# MIDI_Signal_Contidioner.net
KiCad netlist of a schematic drawn in EAGLE
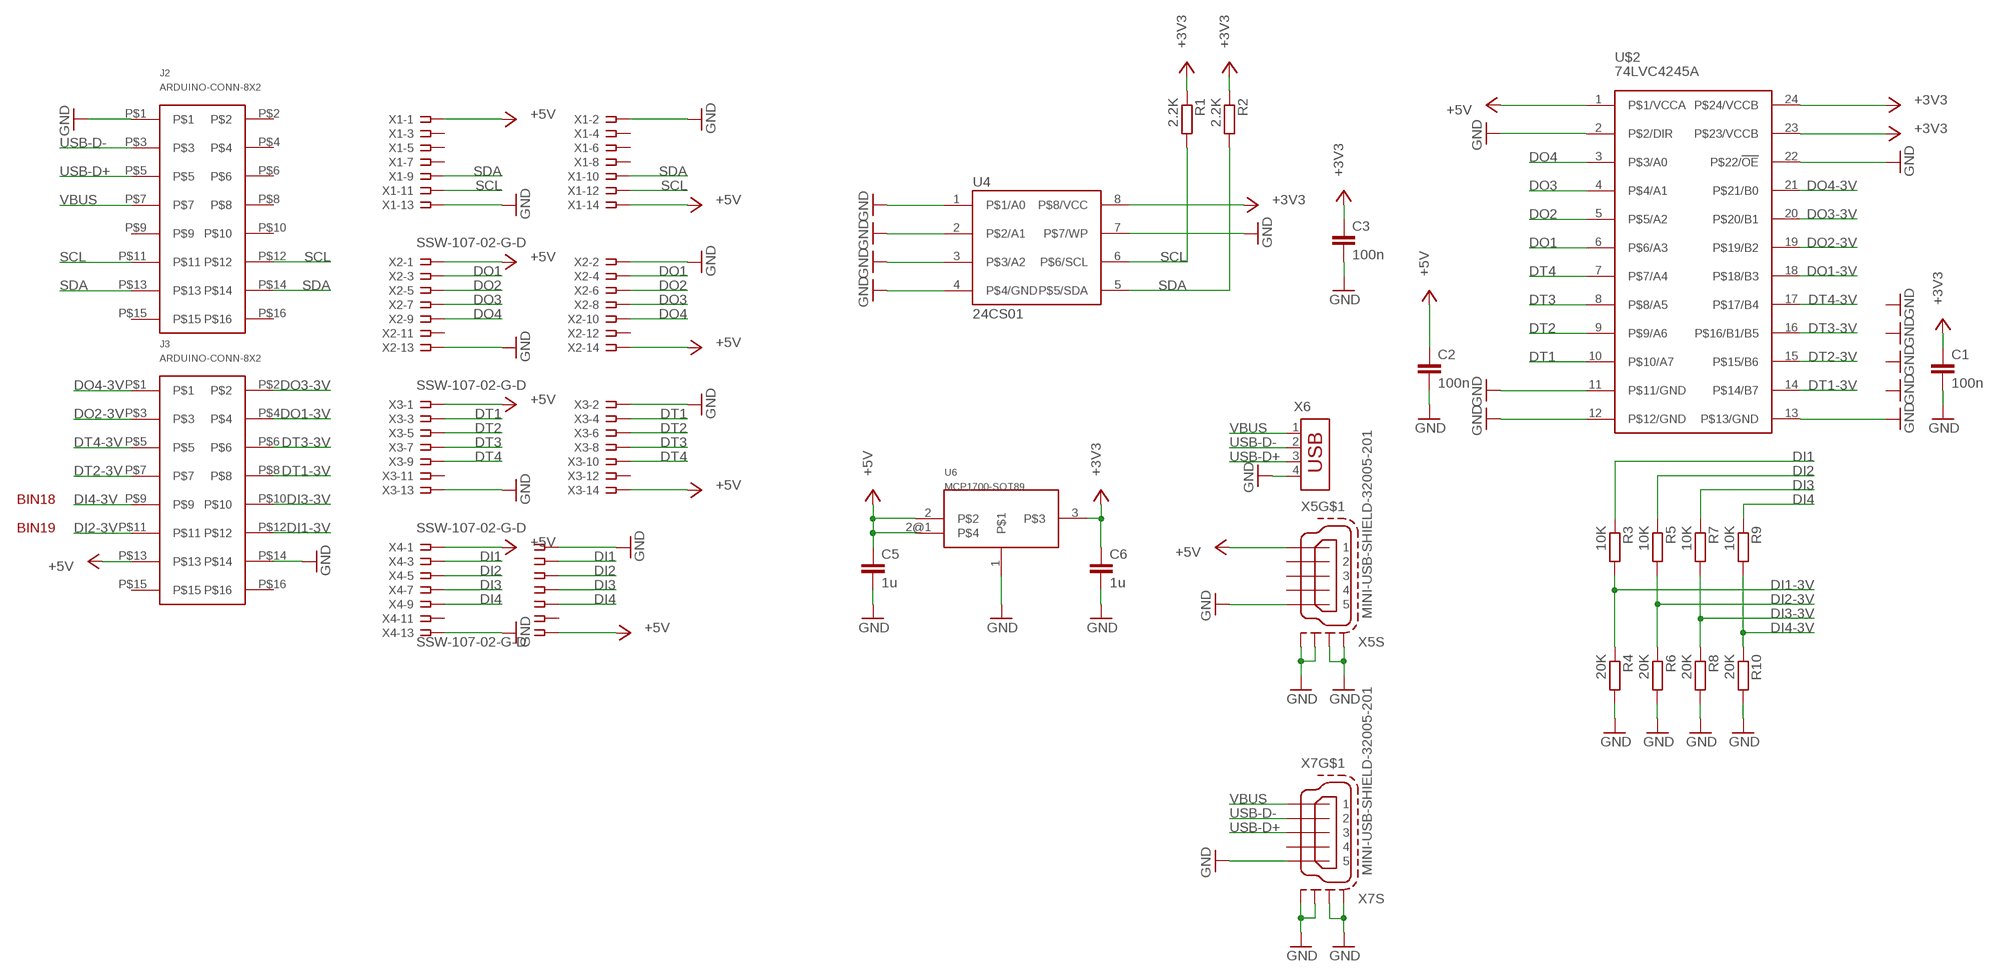
[diagram p0: schematic, sheet 1]

(export (version "E")
  (design (tool "Eeschema 10.0.6"))
  (components
    (comp (ref "C1")
      (value "100n")
      (footprint "eagle-import:C0805")
      (libsource (lib "eagle-import") (part "C-EUC0805"))
    )
    (comp (ref "C2")
      (value "100n")
      (footprint "eagle-import:C0805")
      (libsource (lib "eagle-import") (part "C-EUC0805"))
    )
    (comp (ref "C3")
      (value "100n")
      (footprint "eagle-import:C0805")
      (libsource (lib "eagle-import") (part "C-EUC0805"))
    )
    (comp (ref "C5")
      (value "1u")
      (footprint "eagle-import:C0805")
      (libsource (lib "eagle-import") (part "C-EUC0805"))
    )
    (comp (ref "C6")
      (value "1u")
      (footprint "eagle-import:C0805")
      (libsource (lib "eagle-import") (part "C-EUC0805"))
    )
    (comp (ref "J2")
      (value "ARDUINO-CONN-8X2")
      (footprint "eagle-import:ARDUINO-CONN-8X2")
      (libsource (lib "eagle-import") (part "ARDUINO-CONN-8X2"))
    )
    (comp (ref "J3")
      (value "ARDUINO-CONN-8X2")
      (footprint "eagle-import:ARDUINO-CONN-8X2")
      (libsource (lib "eagle-import") (part "ARDUINO-CONN-8X2"))
    )
    (comp (ref "R1")
      (value "2.2K")
      (footprint "eagle-import:R0805W")
      (libsource (lib "eagle-import") (part "R-EU_R0805W"))
    )
    (comp (ref "R2")
      (value "2.2K")
      (footprint "eagle-import:R0805W")
      (libsource (lib "eagle-import") (part "R-EU_R0805W"))
    )
    (comp (ref "R3")
      (value "10K")
      (footprint "eagle-import:R0805W")
      (libsource (lib "eagle-import") (part "R-EU_R0805W"))
    )
    (comp (ref "R4")
      (value "20K")
      (footprint "eagle-import:R0805W")
      (libsource (lib "eagle-import") (part "R-EU_R0805W"))
    )
    (comp (ref "R5")
      (value "10K")
      (footprint "eagle-import:R0805W")
      (libsource (lib "eagle-import") (part "R-EU_R0805W"))
    )
    (comp (ref "R6")
      (value "20K")
      (footprint "eagle-import:R0805W")
      (libsource (lib "eagle-import") (part "R-EU_R0805W"))
    )
    (comp (ref "R7")
      (value "10K")
      (footprint "eagle-import:R0805W")
      (libsource (lib "eagle-import") (part "R-EU_R0805W"))
    )
    (comp (ref "R8")
      (value "20K")
      (footprint "eagle-import:R0805W")
      (libsource (lib "eagle-import") (part "R-EU_R0805W"))
    )
    (comp (ref "R9")
      (value "10K")
      (footprint "eagle-import:R0805W")
      (libsource (lib "eagle-import") (part "R-EU_R0805W"))
    )
    (comp (ref "R10")
      (value "20K")
      (footprint "eagle-import:R0805W")
      (libsource (lib "eagle-import") (part "R-EU_R0805W"))
    )
    (comp (ref "U$2")
      (value "74LVC4245A")
      (footprint "eagle-import:74LVC4245A-SO24")
      (libsource (lib "eagle-import") (part "74LVC4245A"))
    )
    (comp (ref "U4")
      (value "24CS01")
      (footprint "eagle-import:24CS01-SO8")
      (libsource (lib "eagle-import") (part "24CS01"))
    )
    (comp (ref "U6")
      (value "MCP1700-SOT89")
      (footprint "eagle-import:MCP1700-SOT89")
      (libsource (lib "eagle-import") (part "MCP1700-SOT89"))
    )
    (comp (ref "X1")
      (value "SSW-107-02-G-D")
      (footprint "eagle-import:SSW-107-02-G-D")
      (fields (field (name "MF") "Samtec Inc."))
      (libsource (lib "eagle-import") (part "SSW-107-02-G-D"))
    )
    (comp (ref "X2")
      (value "SSW-107-02-G-D")
      (footprint "eagle-import:SSW-107-02-G-D")
      (fields (field (name "MF") "Samtec Inc."))
      (libsource (lib "eagle-import") (part "SSW-107-02-G-D"))
    )
    (comp (ref "X3")
      (value "SSW-107-02-G-D")
      (footprint "eagle-import:SSW-107-02-G-D")
      (fields (field (name "MF") "Samtec Inc."))
      (libsource (lib "eagle-import") (part "SSW-107-02-G-D"))
    )
    (comp (ref "X4")
      (value "SSW-107-02-G-D")
      (footprint "eagle-import:SSW-107-02-G-D")
      (fields (field (name "MF") "Samtec Inc."))
      (libsource (lib "eagle-import") (part "SSW-107-02-G-D"))
    )
    (comp (ref "X5")
      (value "MINI-USB-SHIELD-32005-201")
      (footprint "eagle-import:MINI-USB-32005-201")
      (libsource (lib "eagle-import") (part "MINI-USB-SHIELD-32005-201"))
    )
    (comp (ref "X6")
      (value "USB-787616")
      (footprint "eagle-import:USB")
      (libsource (lib "eagle-import") (part "USB-787616"))
    )
    (comp (ref "X7")
      (value "MINI-USB-SHIELD-32005-201")
      (footprint "eagle-import:MINI-USB-32005-201")
      (libsource (lib "eagle-import") (part "MINI-USB-SHIELD-32005-201"))
    )
  )
  (nets
    (net (code "1") (name "+3V3") (class "Default")
      (node (ref "C1") (pin "1") (pinfunction "1_1") (pintype "passive"))
      (node (ref "C3") (pin "1") (pinfunction "1_1") (pintype "passive"))
      (node (ref "C6") (pin "1") (pinfunction "1_1") (pintype "passive"))
      (node (ref "R1") (pin "1") (pinfunction "1_1") (pintype "passive"))
      (node (ref "R2") (pin "1") (pinfunction "1_1") (pintype "passive"))
      (node (ref "U$2") (pin "23") (pinfunction "P$23/VCCB_23") (pintype "bidirectional"))
      (node (ref "U$2") (pin "24") (pinfunction "P$24/VCCB_24") (pintype "bidirectional"))
      (node (ref "U4") (pin "8") (pinfunction "P$8/VCC_8") (pintype "bidirectional"))
      (node (ref "U6") (pin "3") (pinfunction "P$3_3") (pintype "bidirectional"))
    )
    (net (code "2") (name "+5V") (class "Default")
      (node (ref "C2") (pin "1") (pinfunction "1_1") (pintype "passive"))
      (node (ref "C5") (pin "1") (pinfunction "1_1") (pintype "passive"))
      (node (ref "J3") (pin "P$13") (pinfunction "P$13_P$13") (pintype "bidirectional"))
      (node (ref "U$2") (pin "1") (pinfunction "P$1/VCCA_1") (pintype "bidirectional"))
      (node (ref "U6") (pin "2") (pinfunction "P$2_2") (pintype "bidirectional"))
      (node (ref "U6") (pin "2@1") (pinfunction "P$4_2@1") (pintype "bidirectional"))
      (node (ref "X1") (pin "1") (pinfunction "1_1") (pintype "passive"))
      (node (ref "X1") (pin "14") (pinfunction "1_14") (pintype "passive"))
      (node (ref "X2") (pin "1") (pinfunction "1_1") (pintype "passive"))
      (node (ref "X2") (pin "14") (pinfunction "1_14") (pintype "passive"))
      (node (ref "X3") (pin "1") (pinfunction "1_1") (pintype "passive"))
      (node (ref "X3") (pin "14") (pinfunction "1_14") (pintype "passive"))
      (node (ref "X4") (pin "1") (pinfunction "1_1") (pintype "passive"))
      (node (ref "X4") (pin "14") (pinfunction "1_14") (pintype "passive"))
      (node (ref "X5") (pin "1") (pinfunction "1_1") (pintype "passive"))
    )
    (net (code "3") (name "/DI1") (class "Default")
      (node (ref "R3") (pin "1") (pinfunction "1_1") (pintype "passive"))
      (node (ref "X4") (pin "3") (pinfunction "1_3") (pintype "passive"))
      (node (ref "X4") (pin "4") (pinfunction "1_4") (pintype "passive"))
    )
    (net (code "4") (name "/DI1-3V") (class "Default")
      (node (ref "J3") (pin "P$12") (pinfunction "P$12_P$12") (pintype "bidirectional"))
      (node (ref "R3") (pin "2") (pinfunction "2_2") (pintype "passive"))
      (node (ref "R4") (pin "1") (pinfunction "1_1") (pintype "passive"))
    )
    (net (code "5") (name "/DI2") (class "Default")
      (node (ref "R5") (pin "1") (pinfunction "1_1") (pintype "passive"))
      (node (ref "X4") (pin "5") (pinfunction "1_5") (pintype "passive"))
      (node (ref "X4") (pin "6") (pinfunction "1_6") (pintype "passive"))
    )
    (net (code "6") (name "/DI2-3V") (class "Default")
      (node (ref "J3") (pin "P$11") (pinfunction "P$11_P$11") (pintype "bidirectional"))
      (node (ref "R5") (pin "2") (pinfunction "2_2") (pintype "passive"))
      (node (ref "R6") (pin "1") (pinfunction "1_1") (pintype "passive"))
    )
    (net (code "7") (name "/DI3") (class "Default")
      (node (ref "R7") (pin "1") (pinfunction "1_1") (pintype "passive"))
      (node (ref "X4") (pin "7") (pinfunction "1_7") (pintype "passive"))
      (node (ref "X4") (pin "8") (pinfunction "1_8") (pintype "passive"))
    )
    (net (code "8") (name "/DI3-3V") (class "Default")
      (node (ref "J3") (pin "P$10") (pinfunction "P$10_P$10") (pintype "bidirectional"))
      (node (ref "R7") (pin "2") (pinfunction "2_2") (pintype "passive"))
      (node (ref "R8") (pin "1") (pinfunction "1_1") (pintype "passive"))
    )
    (net (code "9") (name "/DI4") (class "Default")
      (node (ref "R9") (pin "1") (pinfunction "1_1") (pintype "passive"))
      (node (ref "X4") (pin "10") (pinfunction "1_10") (pintype "passive"))
      (node (ref "X4") (pin "9") (pinfunction "1_9") (pintype "passive"))
    )
    (net (code "10") (name "/DI4-3V") (class "Default")
      (node (ref "J3") (pin "P$9") (pinfunction "P$9_P$9") (pintype "bidirectional"))
      (node (ref "R10") (pin "1") (pinfunction "1_1") (pintype "passive"))
      (node (ref "R9") (pin "2") (pinfunction "2_2") (pintype "passive"))
    )
    (net (code "11") (name "/DO1") (class "Default")
      (node (ref "U$2") (pin "6") (pinfunction "P$6/A3_6") (pintype "bidirectional"))
      (node (ref "X2") (pin "3") (pinfunction "1_3") (pintype "passive"))
      (node (ref "X2") (pin "4") (pinfunction "1_4") (pintype "passive"))
    )
    (net (code "12") (name "/DO1-3V") (class "Default")
      (node (ref "J3") (pin "P$4") (pinfunction "P$4_P$4") (pintype "bidirectional"))
      (node (ref "U$2") (pin "18") (pinfunction "P$18/B3_18") (pintype "bidirectional"))
    )
    (net (code "13") (name "/DO2") (class "Default")
      (node (ref "U$2") (pin "5") (pinfunction "P$5/A2_5") (pintype "bidirectional"))
      (node (ref "X2") (pin "5") (pinfunction "1_5") (pintype "passive"))
      (node (ref "X2") (pin "6") (pinfunction "1_6") (pintype "passive"))
    )
    (net (code "14") (name "/DO2-3V") (class "Default")
      (node (ref "J3") (pin "P$3") (pinfunction "P$3_P$3") (pintype "bidirectional"))
      (node (ref "U$2") (pin "19") (pinfunction "P$19/B2_19") (pintype "bidirectional"))
    )
    (net (code "15") (name "/DO3") (class "Default")
      (node (ref "U$2") (pin "4") (pinfunction "P$4/A1_4") (pintype "bidirectional"))
      (node (ref "X2") (pin "7") (pinfunction "1_7") (pintype "passive"))
      (node (ref "X2") (pin "8") (pinfunction "1_8") (pintype "passive"))
    )
    (net (code "16") (name "/DO3-3V") (class "Default")
      (node (ref "J3") (pin "P$2") (pinfunction "P$2_P$2") (pintype "bidirectional"))
      (node (ref "U$2") (pin "20") (pinfunction "P$20/B1_20") (pintype "bidirectional"))
    )
    (net (code "17") (name "/DO4") (class "Default")
      (node (ref "U$2") (pin "3") (pinfunction "P$3/A0_3") (pintype "bidirectional"))
      (node (ref "X2") (pin "10") (pinfunction "1_10") (pintype "passive"))
      (node (ref "X2") (pin "9") (pinfunction "1_9") (pintype "passive"))
    )
    (net (code "18") (name "/DO4-3V") (class "Default")
      (node (ref "J3") (pin "P$1") (pinfunction "P$1_P$1") (pintype "bidirectional"))
      (node (ref "U$2") (pin "21") (pinfunction "P$21/B0_21") (pintype "bidirectional"))
    )
    (net (code "19") (name "/DT1") (class "Default")
      (node (ref "U$2") (pin "10") (pinfunction "P$10/A7_10") (pintype "bidirectional"))
      (node (ref "X3") (pin "3") (pinfunction "1_3") (pintype "passive"))
      (node (ref "X3") (pin "4") (pinfunction "1_4") (pintype "passive"))
    )
    (net (code "20") (name "/DT1-3V") (class "Default")
      (node (ref "J3") (pin "P$8") (pinfunction "P$8_P$8") (pintype "bidirectional"))
      (node (ref "U$2") (pin "14") (pinfunction "P$14/B7_14") (pintype "bidirectional"))
    )
    (net (code "21") (name "/DT2") (class "Default")
      (node (ref "U$2") (pin "9") (pinfunction "P$9/A6_9") (pintype "bidirectional"))
      (node (ref "X3") (pin "5") (pinfunction "1_5") (pintype "passive"))
      (node (ref "X3") (pin "6") (pinfunction "1_6") (pintype "passive"))
    )
    (net (code "22") (name "/DT2-3V") (class "Default")
      (node (ref "J3") (pin "P$7") (pinfunction "P$7_P$7") (pintype "bidirectional"))
      (node (ref "U$2") (pin "15") (pinfunction "P$15/B6_15") (pintype "bidirectional"))
    )
    (net (code "23") (name "/DT3") (class "Default")
      (node (ref "U$2") (pin "8") (pinfunction "P$8/A5_8") (pintype "bidirectional"))
      (node (ref "X3") (pin "7") (pinfunction "1_7") (pintype "passive"))
      (node (ref "X3") (pin "8") (pinfunction "1_8") (pintype "passive"))
    )
    (net (code "24") (name "/DT3-3V") (class "Default")
      (node (ref "J3") (pin "P$6") (pinfunction "P$6_P$6") (pintype "bidirectional"))
      (node (ref "U$2") (pin "16") (pinfunction "P$16/B1/B5_16") (pintype "bidirectional"))
    )
    (net (code "25") (name "/DT4") (class "Default")
      (node (ref "U$2") (pin "7") (pinfunction "P$7/A4_7") (pintype "bidirectional"))
      (node (ref "X3") (pin "10") (pinfunction "1_10") (pintype "passive"))
      (node (ref "X3") (pin "9") (pinfunction "1_9") (pintype "passive"))
    )
    (net (code "26") (name "/DT4-3V") (class "Default")
      (node (ref "J3") (pin "P$5") (pinfunction "P$5_P$5") (pintype "bidirectional"))
      (node (ref "U$2") (pin "17") (pinfunction "P$17/B4_17") (pintype "bidirectional"))
    )
    (net (code "27") (name "/SCL") (class "Default")
      (node (ref "J2") (pin "P$11") (pinfunction "P$11_P$11") (pintype "bidirectional"))
      (node (ref "J2") (pin "P$12") (pinfunction "P$12_P$12") (pintype "bidirectional"))
      (node (ref "R1") (pin "2") (pinfunction "2_2") (pintype "passive"))
      (node (ref "U4") (pin "6") (pinfunction "P$6/SCL_6") (pintype "bidirectional"))
      (node (ref "X1") (pin "11") (pinfunction "1_11") (pintype "passive"))
      (node (ref "X1") (pin "12") (pinfunction "1_12") (pintype "passive"))
    )
    (net (code "28") (name "/SDA") (class "Default")
      (node (ref "J2") (pin "P$13") (pinfunction "P$13_P$13") (pintype "bidirectional"))
      (node (ref "J2") (pin "P$14") (pinfunction "P$14_P$14") (pintype "bidirectional"))
      (node (ref "R2") (pin "2") (pinfunction "2_2") (pintype "passive"))
      (node (ref "U4") (pin "5") (pinfunction "P$5/SDA_5") (pintype "bidirectional"))
      (node (ref "X1") (pin "10") (pinfunction "1_10") (pintype "passive"))
      (node (ref "X1") (pin "9") (pinfunction "1_9") (pintype "passive"))
    )
    (net (code "29") (name "/USB-D+") (class "Default")
      (node (ref "J2") (pin "P$5") (pinfunction "P$5_P$5") (pintype "bidirectional"))
      (node (ref "X6") (pin "3") (pinfunction "3_3") (pintype "passive"))
      (node (ref "X7") (pin "3") (pinfunction "3_3") (pintype "passive"))
    )
    (net (code "30") (name "/USB-D-") (class "Default")
      (node (ref "J2") (pin "P$3") (pinfunction "P$3_P$3") (pintype "bidirectional"))
      (node (ref "X6") (pin "2") (pinfunction "2_2") (pintype "passive"))
      (node (ref "X7") (pin "2") (pinfunction "2_2") (pintype "passive"))
    )
    (net (code "31") (name "/VBUS") (class "Default")
      (node (ref "J2") (pin "P$7") (pinfunction "P$7_P$7") (pintype "bidirectional"))
      (node (ref "X6") (pin "1") (pinfunction "1_1") (pintype "passive"))
      (node (ref "X7") (pin "1") (pinfunction "1_1") (pintype "passive"))
    )
    (net (code "32") (name "GND") (class "Default")
      (node (ref "C1") (pin "2") (pinfunction "2_2") (pintype "passive"))
      (node (ref "C2") (pin "2") (pinfunction "2_2") (pintype "passive"))
      (node (ref "C3") (pin "2") (pinfunction "2_2") (pintype "passive"))
      (node (ref "C5") (pin "2") (pinfunction "2_2") (pintype "passive"))
      (node (ref "C6") (pin "2") (pinfunction "2_2") (pintype "passive"))
      (node (ref "J2") (pin "P$1") (pinfunction "P$1_P$1") (pintype "bidirectional"))
      (node (ref "J3") (pin "P$14") (pinfunction "P$14_P$14") (pintype "bidirectional"))
      (node (ref "R10") (pin "2") (pinfunction "2_2") (pintype "passive"))
      (node (ref "R4") (pin "2") (pinfunction "2_2") (pintype "passive"))
      (node (ref "R6") (pin "2") (pinfunction "2_2") (pintype "passive"))
      (node (ref "R8") (pin "2") (pinfunction "2_2") (pintype "passive"))
      (node (ref "U$2") (pin "11") (pinfunction "P$11/GND_11") (pintype "bidirectional"))
      (node (ref "U$2") (pin "12") (pinfunction "P$12/GND_12") (pintype "bidirectional"))
      (node (ref "U$2") (pin "13") (pinfunction "P$13/GND_13") (pintype "bidirectional"))
      (node (ref "U$2") (pin "2") (pinfunction "P$2/DIR_2") (pintype "bidirectional"))
      (node (ref "U$2") (pin "22") (pinfunction "P$22/~{OE}_22") (pintype "bidirectional"))
      (node (ref "U4") (pin "1") (pinfunction "P$1/A0_1") (pintype "bidirectional"))
      (node (ref "U4") (pin "2") (pinfunction "P$2/A1_2") (pintype "bidirectional"))
      (node (ref "U4") (pin "3") (pinfunction "P$3/A2_3") (pintype "bidirectional"))
      (node (ref "U4") (pin "4") (pinfunction "P$4/GND_4") (pintype "bidirectional"))
      (node (ref "U4") (pin "7") (pinfunction "P$7/WP_7") (pintype "bidirectional"))
      (node (ref "U6") (pin "1") (pinfunction "P$1_1") (pintype "bidirectional"))
      (node (ref "X1") (pin "13") (pinfunction "1_13") (pintype "passive"))
      (node (ref "X1") (pin "2") (pinfunction "1_2") (pintype "passive"))
      (node (ref "X2") (pin "13") (pinfunction "1_13") (pintype "passive"))
      (node (ref "X2") (pin "2") (pinfunction "1_2") (pintype "passive"))
      (node (ref "X3") (pin "13") (pinfunction "1_13") (pintype "passive"))
      (node (ref "X3") (pin "2") (pinfunction "1_2") (pintype "passive"))
      (node (ref "X4") (pin "13") (pinfunction "1_13") (pintype "passive"))
      (node (ref "X4") (pin "2") (pinfunction "1_2") (pintype "passive"))
      (node (ref "X5") (pin "5") (pinfunction "5_5") (pintype "passive"))
      (node (ref "X5") (pin "M1") (pinfunction "S1_M1") (pintype "passive"))
      (node (ref "X5") (pin "M2") (pinfunction "S2_M2") (pintype "passive"))
      (node (ref "X5") (pin "M3") (pinfunction "S3_M3") (pintype "passive"))
      (node (ref "X5") (pin "M4") (pinfunction "S4_M4") (pintype "passive"))
      (node (ref "X6") (pin "4") (pinfunction "4_4") (pintype "passive"))
      (node (ref "X7") (pin "5") (pinfunction "5_5") (pintype "passive"))
      (node (ref "X7") (pin "M1") (pinfunction "S1_M1") (pintype "passive"))
      (node (ref "X7") (pin "M2") (pinfunction "S2_M2") (pintype "passive"))
      (node (ref "X7") (pin "M3") (pinfunction "S3_M3") (pintype "passive"))
      (node (ref "X7") (pin "M4") (pinfunction "S4_M4") (pintype "passive"))
    )
    (net (code "33") (name "unconnected-(J2-PadP$2)") (class "Default")
      (node (ref "J2") (pin "P$2") (pinfunction "P$2_P$2") (pintype "bidirectional"))
    )
    (net (code "34") (name "unconnected-(J2-PadP$4)") (class "Default")
      (node (ref "J2") (pin "P$4") (pinfunction "P$4_P$4") (pintype "bidirectional"))
    )
    (net (code "35") (name "unconnected-(J2-PadP$6)") (class "Default")
      (node (ref "J2") (pin "P$6") (pinfunction "P$6_P$6") (pintype "bidirectional"))
    )
    (net (code "36") (name "unconnected-(J2-PadP$8)") (class "Default")
      (node (ref "J2") (pin "P$8") (pinfunction "P$8_P$8") (pintype "bidirectional"))
    )
    (net (code "37") (name "unconnected-(J2-PadP$9)") (class "Default")
      (node (ref "J2") (pin "P$9") (pinfunction "P$9_P$9") (pintype "bidirectional"))
    )
    (net (code "38") (name "unconnected-(J2-PadP$10)") (class "Default")
      (node (ref "J2") (pin "P$10") (pinfunction "P$10_P$10") (pintype "bidirectional"))
    )
    (net (code "39") (name "unconnected-(J2-PadP$15)") (class "Default")
      (node (ref "J2") (pin "P$15") (pinfunction "P$15_P$15") (pintype "bidirectional"))
    )
    (net (code "40") (name "unconnected-(J2-PadP$16)") (class "Default")
      (node (ref "J2") (pin "P$16") (pinfunction "P$16_P$16") (pintype "bidirectional"))
    )
    (net (code "41") (name "unconnected-(J3-PadP$15)") (class "Default")
      (node (ref "J3") (pin "P$15") (pinfunction "P$15_P$15") (pintype "bidirectional"))
    )
    (net (code "42") (name "unconnected-(J3-PadP$16)") (class "Default")
      (node (ref "J3") (pin "P$16") (pinfunction "P$16_P$16") (pintype "bidirectional"))
    )
    (net (code "43") (name "unconnected-(X1H-1-Pad3)") (class "Default")
      (node (ref "X1") (pin "3") (pinfunction "1_3") (pintype "passive"))
    )
    (net (code "44") (name "unconnected-(X1I-1-Pad4)") (class "Default")
      (node (ref "X1") (pin "4") (pinfunction "1_4") (pintype "passive"))
    )
    (net (code "45") (name "unconnected-(X1J-1-Pad5)") (class "Default")
      (node (ref "X1") (pin "5") (pinfunction "1_5") (pintype "passive"))
    )
    (net (code "46") (name "unconnected-(X1K-1-Pad6)") (class "Default")
      (node (ref "X1") (pin "6") (pinfunction "1_6") (pintype "passive"))
    )
    (net (code "47") (name "unconnected-(X1L-1-Pad7)") (class "Default")
      (node (ref "X1") (pin "7") (pinfunction "1_7") (pintype "passive"))
    )
    (net (code "48") (name "unconnected-(X1M-1-Pad8)") (class "Default")
      (node (ref "X1") (pin "8") (pinfunction "1_8") (pintype "passive"))
    )
    (net (code "49") (name "unconnected-(X2C-1-Pad11)") (class "Default")
      (node (ref "X2") (pin "11") (pinfunction "1_11") (pintype "passive"))
    )
    (net (code "50") (name "unconnected-(X2D-1-Pad12)") (class "Default")
      (node (ref "X2") (pin "12") (pinfunction "1_12") (pintype "passive"))
    )
    (net (code "51") (name "unconnected-(X3C-1-Pad11)") (class "Default")
      (node (ref "X3") (pin "11") (pinfunction "1_11") (pintype "passive"))
    )
    (net (code "52") (name "unconnected-(X3D-1-Pad12)") (class "Default")
      (node (ref "X3") (pin "12") (pinfunction "1_12") (pintype "passive"))
    )
    (net (code "53") (name "unconnected-(X4C-1-Pad11)") (class "Default")
      (node (ref "X4") (pin "11") (pinfunction "1_11") (pintype "passive"))
    )
    (net (code "54") (name "unconnected-(X4D-1-Pad12)") (class "Default")
      (node (ref "X4") (pin "12") (pinfunction "1_12") (pintype "passive"))
    )
    (net (code "55") (name "unconnected-(X5-Pad2)") (class "Default")
      (node (ref "X5") (pin "2") (pinfunction "2_2") (pintype "passive"))
    )
    (net (code "56") (name "unconnected-(X5-Pad3)") (class "Default")
      (node (ref "X5") (pin "3") (pinfunction "3_3") (pintype "passive"))
    )
    (net (code "57") (name "unconnected-(X5-Pad4)") (class "Default")
      (node (ref "X5") (pin "4") (pinfunction "4_4") (pintype "passive"))
    )
    (net (code "58") (name "unconnected-(X7-Pad4)") (class "Default")
      (node (ref "X7") (pin "4") (pinfunction "4_4") (pintype "passive"))
    )
  )
)
